# Sheet1.net
KiCad netlist of a schematic drawn in Altium Designer
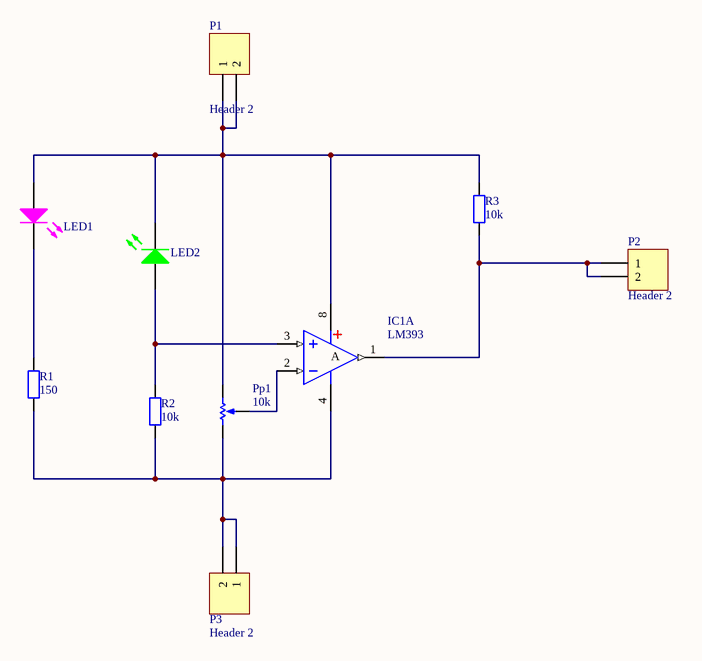
[diagram p0: Sheet1.SchDoc]

(export (version "E")
  (design (tool "Eeschema 10.0.6"))
  (components
    (comp (ref "IC1")
      (value "LM393")
      (footprint "DIP8-300")
      (description "双路电压比较")
      (fields (field (name "版权归属") "源创客"))
      (libsource (lib "IC芯片") (part "LM393"))
    )
    (comp (ref "LED1")
      (value "LED-3-R")
      (footprint "LED-R3-H5-SINGLE-R")
      (description "Typical INFRARED GaAs LED")
      (fields (field (name "PUBLISHER") "Altium Limited"))
      (libsource (lib "03-EButterflyIntegratedLibrary") (part "LED-3-R"))
    )
    (comp (ref "LED2")
      (value "LED-3-G")
      (footprint "LED-R3-H5-SINGLE-G")
      (description "Typical INFRARED GaAs LED")
      (fields (field (name "PUBLISHER") "Altium Limited"))
      (libsource (lib "03-EButterflyIntegratedLibrary") (part "LED-3-G"))
    )
    (comp (ref "P1")
      (value "Header 2")
      (footprint "HDR1X2")
      (description "Header, 2-Pin")
      (fields (field (name "PUBLISHER") "Altium Limited"))
      (libsource (lib "") (part "Header 2_1"))
    )
    (comp (ref "P2")
      (value "Header 2")
      (footprint "HDR1X2")
      (description "Header, 2-Pin")
      (fields (field (name "PUBLISHER") "Altium Limited"))
      (libsource (lib "") (part "Header 2_2"))
    )
    (comp (ref "P3")
      (value "Header 2")
      (footprint "HDR1X2")
      (description "Header, 2-Pin")
      (fields (field (name "PUBLISHER") "Altium Limited"))
      (libsource (lib "03-EButterflyIntegratedLibrary") (part "Header 2"))
    )
    (comp (ref "Pp1")
      (value "10k")
      (footprint "RP_3296")
      (description "3296电位器")
      (libsource (lib "02-Miscellaneous_Devices_ZSF_Library") (part "RP_3296"))
    )
    (comp (ref "R1")
      (value "150")
      (footprint "AXIAL-0.3")
      (description "Resistor")
      (fields (field (name "PUBLISHER") "Altium Limited"))
      (libsource (lib "03-EButterflyIntegratedLibrary") (part "Resistor"))
    )
    (comp (ref "R2")
      (value "10k")
      (footprint "AXIAL-0.3")
      (description "Resistor")
      (fields (field (name "PUBLISHER") "Altium Limited"))
      (libsource (lib "03-EButterflyIntegratedLibrary") (part "Resistor"))
    )
    (comp (ref "R3")
      (value "10k")
      (footprint "AXIAL-0.3")
      (description "Resistor")
      (fields (field (name "PUBLISHER") "Altium Limited"))
      (libsource (lib "03-EButterflyIntegratedLibrary") (part "Resistor"))
    )
  )
  (nets
    (net (code "1") (name "Net-(IC1A-IN+)") (class "Default")
      (node (ref "IC1") (pin "3") (pinfunction "IN+_3") (pintype "input"))
      (node (ref "LED2") (pin "1") (pinfunction "A_1") (pintype "passive"))
      (node (ref "R2") (pin "2") (pinfunction "2_2") (pintype "passive"))
    )
    (net (code "2") (name "Net-(IC1A-IN-)") (class "Default")
      (node (ref "IC1") (pin "2") (pinfunction "IN-_2") (pintype "input"))
      (node (ref "Pp1") (pin "2") (pinfunction "TAP_2") (pintype "passive"))
    )
    (net (code "3") (name "Net-(IC1A-OUT)") (class "Default")
      (node (ref "IC1") (pin "1") (pinfunction "OUT_1") (pintype "output"))
      (node (ref "P2") (pin "1") (pinfunction "1_1") (pintype "passive"))
      (node (ref "P2") (pin "2") (pinfunction "2_2") (pintype "passive"))
      (node (ref "R3") (pin "1") (pinfunction "1_1") (pintype "passive"))
    )
    (net (code "4") (name "Net-(IC1A-V+)") (class "Default")
      (node (ref "IC1") (pin "8") (pinfunction "V+_8") (pintype "power_in"))
      (node (ref "LED1") (pin "1") (pinfunction "A_1") (pintype "passive"))
      (node (ref "LED2") (pin "2") (pinfunction "K_2") (pintype "passive"))
      (node (ref "P1") (pin "1") (pinfunction "1_1") (pintype "passive"))
      (node (ref "P1") (pin "2") (pinfunction "2_2") (pintype "passive"))
      (node (ref "Pp1") (pin "3") (pinfunction "BOT_3") (pintype "passive"))
      (node (ref "R3") (pin "2") (pinfunction "2_2") (pintype "passive"))
    )
    (net (code "5") (name "Net-(IC1A-V-)") (class "Default")
      (node (ref "IC1") (pin "4") (pinfunction "V-_4") (pintype "power_in"))
      (node (ref "P3") (pin "1") (pinfunction "1_1") (pintype "passive"))
      (node (ref "P3") (pin "2") (pinfunction "2_2") (pintype "passive"))
      (node (ref "Pp1") (pin "1") (pinfunction "TOP_1") (pintype "passive"))
      (node (ref "R1") (pin "1") (pinfunction "1_1") (pintype "passive"))
      (node (ref "R2") (pin "1") (pinfunction "1_1") (pintype "passive"))
    )
    (net (code "6") (name "Net-(LED1-K)") (class "Default")
      (node (ref "LED1") (pin "2") (pinfunction "K_2") (pintype "passive"))
      (node (ref "R1") (pin "2") (pinfunction "2_2") (pintype "passive"))
    )
  )
)
